# Arduino_Mega14x_V2.net
KiCad netlist of a schematic drawn in EAGLE
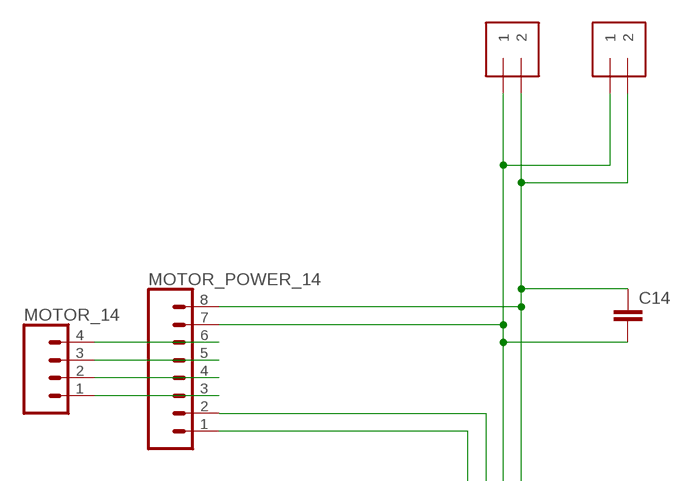
[diagram p0: schematic, sheet 1, part 1 of 3]
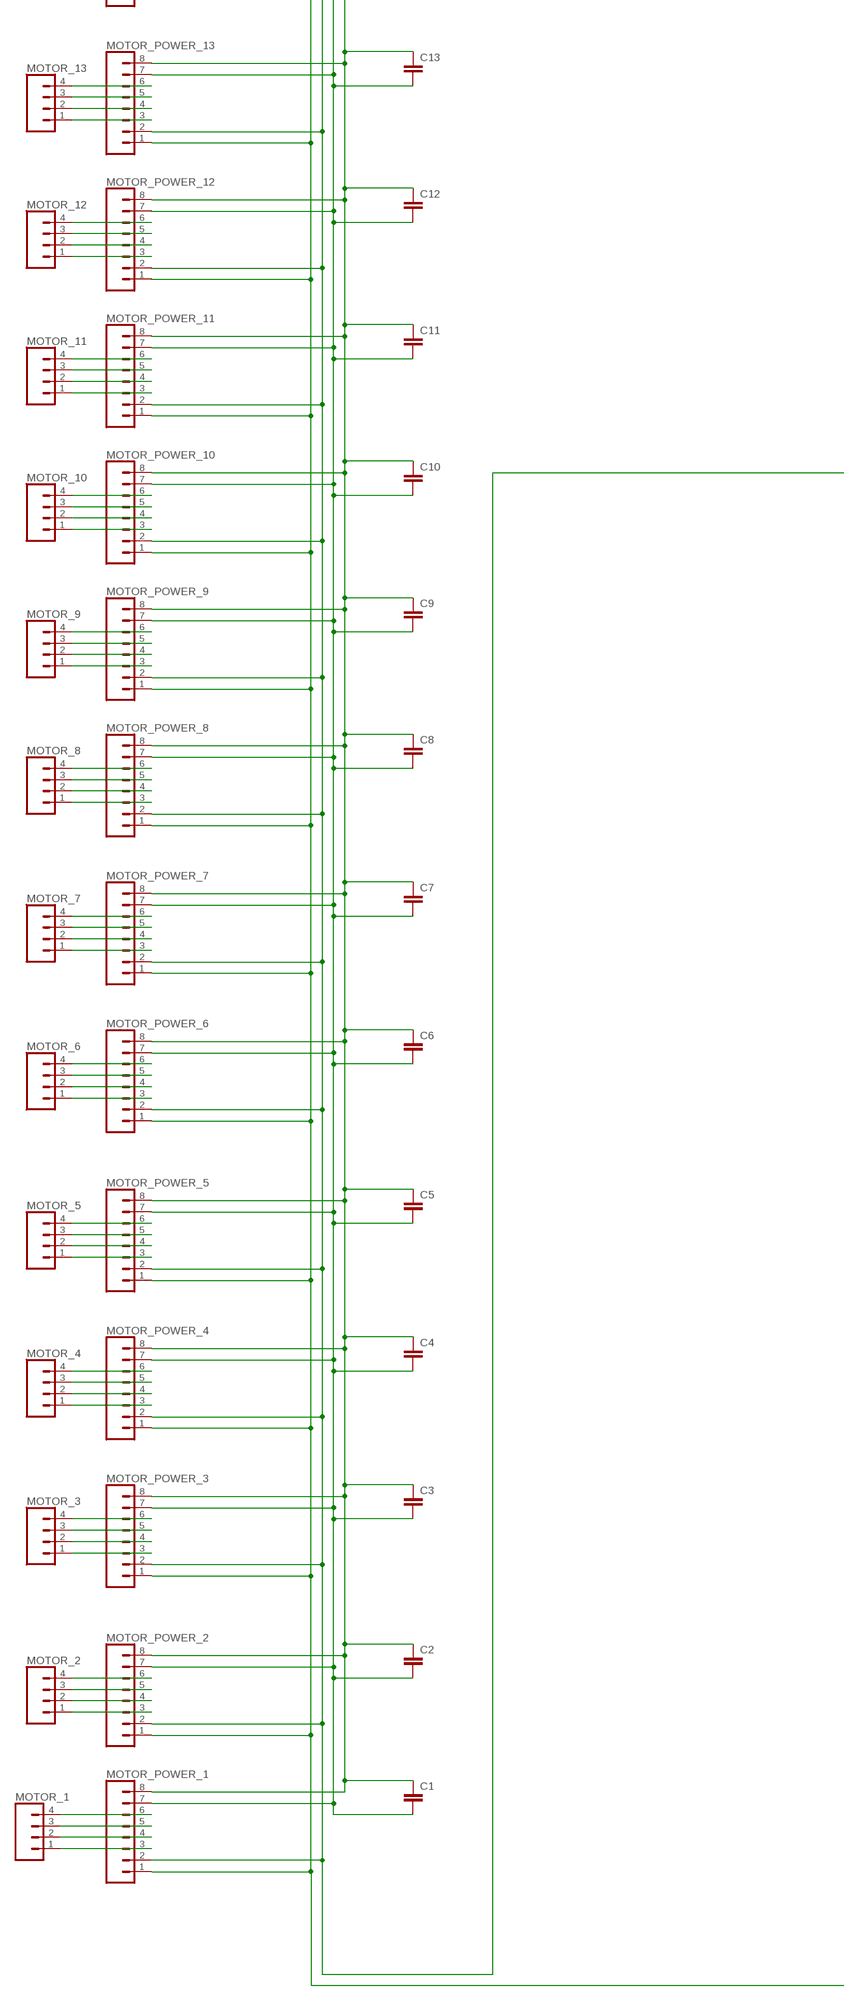
[diagram p1: schematic, sheet 1, part 2 of 3]
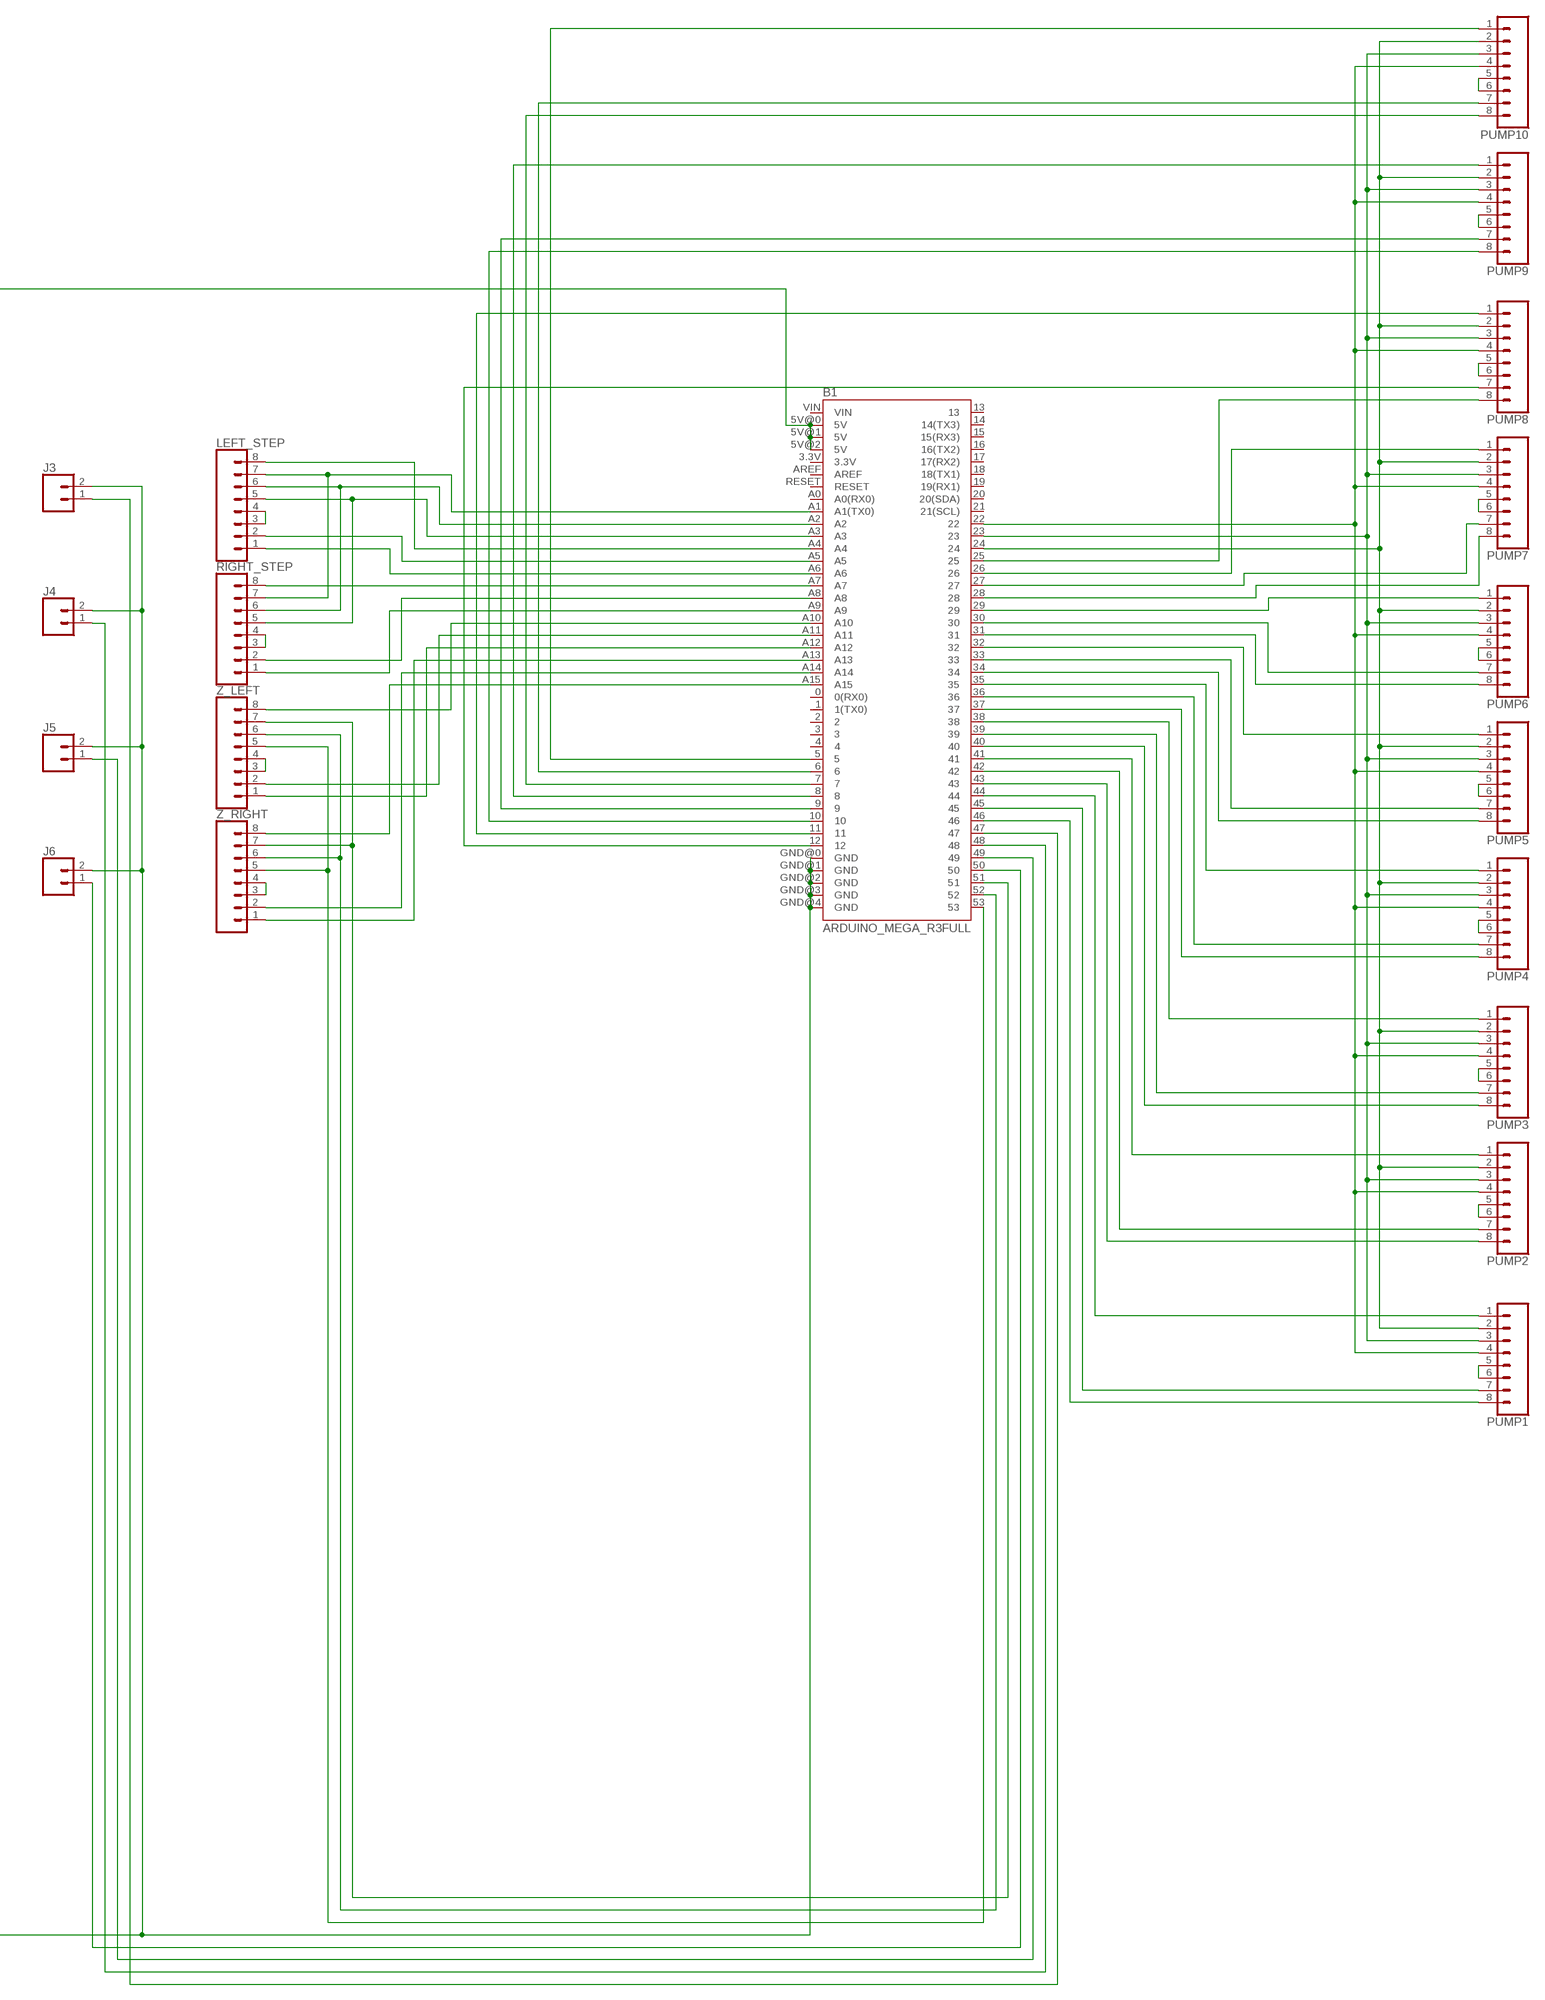
[diagram p2: schematic, sheet 1, part 3 of 3]

(export (version "E")
  (design (tool "Eeschema 10.0.6"))
  (components
    (comp (ref "B1")
      (value "ARDUINO_MEGA_R3FULL")
      (footprint "eagle-import:ARDUINO_MEGA")
      (libsource (lib "eagle-import") (part "ARDUINO_MEGA_R3FULL"))
    )
    (comp (ref "C1")
      (value "C5/2.5")
      (footprint "eagle-import:C5B2.5")
      (libsource (lib "eagle-import") (part "C5/2.5"))
    )
    (comp (ref "C2")
      (value "C5/2.5")
      (footprint "eagle-import:C5B2.5")
      (libsource (lib "eagle-import") (part "C5/2.5"))
    )
    (comp (ref "C3")
      (value "C5/2.5")
      (footprint "eagle-import:C5B2.5")
      (libsource (lib "eagle-import") (part "C5/2.5"))
    )
    (comp (ref "C4")
      (value "C5/2.5")
      (footprint "eagle-import:C5B2.5")
      (libsource (lib "eagle-import") (part "C5/2.5"))
    )
    (comp (ref "C5")
      (value "C5/2.5")
      (footprint "eagle-import:C5B2.5")
      (libsource (lib "eagle-import") (part "C5/2.5"))
    )
    (comp (ref "C6")
      (value "C5/2.5")
      (footprint "eagle-import:C5B2.5")
      (libsource (lib "eagle-import") (part "C5/2.5"))
    )
    (comp (ref "C7")
      (value "C5/2.5")
      (footprint "eagle-import:C5B2.5")
      (libsource (lib "eagle-import") (part "C5/2.5"))
    )
    (comp (ref "C8")
      (value "C5/2.5")
      (footprint "eagle-import:C5B2.5")
      (libsource (lib "eagle-import") (part "C5/2.5"))
    )
    (comp (ref "C9")
      (value "C5/2.5")
      (footprint "eagle-import:C5B2.5")
      (libsource (lib "eagle-import") (part "C5/2.5"))
    )
    (comp (ref "C10")
      (value "C5/2.5")
      (footprint "eagle-import:C5B2.5")
      (libsource (lib "eagle-import") (part "C5/2.5"))
    )
    (comp (ref "C11")
      (value "C5/2.5")
      (footprint "eagle-import:C5B2.5")
      (libsource (lib "eagle-import") (part "C5/2.5"))
    )
    (comp (ref "C12")
      (value "C5/2.5")
      (footprint "eagle-import:C5B2.5")
      (libsource (lib "eagle-import") (part "C5/2.5"))
    )
    (comp (ref "C13")
      (value "C5/2.5")
      (footprint "eagle-import:C5B2.5")
      (libsource (lib "eagle-import") (part "C5/2.5"))
    )
    (comp (ref "C14")
      (value "C5/2.5")
      (footprint "eagle-import:C5B2.5")
      (libsource (lib "eagle-import") (part "C5/2.5"))
    )
    (comp (ref "J1")
      (value "1X2-3.5MM")
      (footprint "eagle-import:1X2-3.5MM")
      (libsource (lib "eagle-import") (part "1X2-3.5MM"))
    )
    (comp (ref "J2")
      (value "1X2-3.5MM")
      (footprint "eagle-import:1X2-3.5MM")
      (libsource (lib "eagle-import") (part "1X2-3.5MM"))
    )
    (comp (ref "J3")
      (value "CONN_02")
      (footprint "eagle-import:1X02")
      (libsource (lib "eagle-import") (part "CONN_02"))
    )
    (comp (ref "J4")
      (value "CONN_02")
      (footprint "eagle-import:1X02")
      (libsource (lib "eagle-import") (part "CONN_02"))
    )
    (comp (ref "J5")
      (value "CONN_02")
      (footprint "eagle-import:1X02")
      (libsource (lib "eagle-import") (part "CONN_02"))
    )
    (comp (ref "J6")
      (value "CONN_02")
      (footprint "eagle-import:1X02")
      (libsource (lib "eagle-import") (part "CONN_02"))
    )
    (comp (ref "LEFT_STEP")
      (value "CONN_08\"")
      (footprint "eagle-import:1X08")
      (libsource (lib "eagle-import") (part "CONN_08{dblquote}"))
    )
    (comp (ref "MOTOR_1")
      (value "CONN_04")
      (footprint "eagle-import:1X04")
      (libsource (lib "eagle-import") (part "CONN_04"))
    )
    (comp (ref "MOTOR_2")
      (value "CONN_04")
      (footprint "eagle-import:1X04")
      (libsource (lib "eagle-import") (part "CONN_04"))
    )
    (comp (ref "MOTOR_3")
      (value "CONN_04")
      (footprint "eagle-import:1X04")
      (libsource (lib "eagle-import") (part "CONN_04"))
    )
    (comp (ref "MOTOR_4")
      (value "CONN_04")
      (footprint "eagle-import:1X04")
      (libsource (lib "eagle-import") (part "CONN_04"))
    )
    (comp (ref "MOTOR_5")
      (value "CONN_04")
      (footprint "eagle-import:1X04")
      (libsource (lib "eagle-import") (part "CONN_04"))
    )
    (comp (ref "MOTOR_6")
      (value "CONN_04")
      (footprint "eagle-import:1X04")
      (libsource (lib "eagle-import") (part "CONN_04"))
    )
    (comp (ref "MOTOR_7")
      (value "CONN_04")
      (footprint "eagle-import:1X04")
      (libsource (lib "eagle-import") (part "CONN_04"))
    )
    (comp (ref "MOTOR_8")
      (value "CONN_04")
      (footprint "eagle-import:1X04")
      (libsource (lib "eagle-import") (part "CONN_04"))
    )
    (comp (ref "MOTOR_9")
      (value "CONN_04")
      (footprint "eagle-import:1X04")
      (libsource (lib "eagle-import") (part "CONN_04"))
    )
    (comp (ref "MOTOR_10")
      (value "CONN_04")
      (footprint "eagle-import:1X04")
      (libsource (lib "eagle-import") (part "CONN_04"))
    )
    (comp (ref "MOTOR_11")
      (value "CONN_04")
      (footprint "eagle-import:1X04")
      (libsource (lib "eagle-import") (part "CONN_04"))
    )
    (comp (ref "MOTOR_12")
      (value "CONN_04")
      (footprint "eagle-import:1X04")
      (libsource (lib "eagle-import") (part "CONN_04"))
    )
    (comp (ref "MOTOR_13")
      (value "CONN_04")
      (footprint "eagle-import:1X04")
      (libsource (lib "eagle-import") (part "CONN_04"))
    )
    (comp (ref "MOTOR_14")
      (value "CONN_04")
      (footprint "eagle-import:1X04")
      (libsource (lib "eagle-import") (part "CONN_04"))
    )
    (comp (ref "MOTOR_POWER_1")
      (value "CONN_08\"")
      (footprint "eagle-import:1X08")
      (libsource (lib "eagle-import") (part "CONN_08{dblquote}"))
    )
    (comp (ref "MOTOR_POWER_2")
      (value "CONN_08\"")
      (footprint "eagle-import:1X08")
      (libsource (lib "eagle-import") (part "CONN_08{dblquote}"))
    )
    (comp (ref "MOTOR_POWER_3")
      (value "CONN_08\"")
      (footprint "eagle-import:1X08")
      (libsource (lib "eagle-import") (part "CONN_08{dblquote}"))
    )
    (comp (ref "MOTOR_POWER_4")
      (value "CONN_08\"")
      (footprint "eagle-import:1X08")
      (libsource (lib "eagle-import") (part "CONN_08{dblquote}"))
    )
    (comp (ref "MOTOR_POWER_5")
      (value "CONN_08\"")
      (footprint "eagle-import:1X08")
      (libsource (lib "eagle-import") (part "CONN_08{dblquote}"))
    )
    (comp (ref "MOTOR_POWER_6")
      (value "CONN_08\"")
      (footprint "eagle-import:1X08")
      (libsource (lib "eagle-import") (part "CONN_08{dblquote}"))
    )
    (comp (ref "MOTOR_POWER_7")
      (value "CONN_08\"")
      (footprint "eagle-import:1X08")
      (libsource (lib "eagle-import") (part "CONN_08{dblquote}"))
    )
    (comp (ref "MOTOR_POWER_8")
      (value "CONN_08\"")
      (footprint "eagle-import:1X08")
      (libsource (lib "eagle-import") (part "CONN_08{dblquote}"))
    )
    (comp (ref "MOTOR_POWER_9")
      (value "CONN_08\"")
      (footprint "eagle-import:1X08")
      (libsource (lib "eagle-import") (part "CONN_08{dblquote}"))
    )
    (comp (ref "MOTOR_POWER_10")
      (value "CONN_08\"")
      (footprint "eagle-import:1X08")
      (libsource (lib "eagle-import") (part "CONN_08{dblquote}"))
    )
    (comp (ref "MOTOR_POWER_11")
      (value "CONN_08\"")
      (footprint "eagle-import:1X08")
      (libsource (lib "eagle-import") (part "CONN_08{dblquote}"))
    )
    (comp (ref "MOTOR_POWER_12")
      (value "CONN_08\"")
      (footprint "eagle-import:1X08")
      (libsource (lib "eagle-import") (part "CONN_08{dblquote}"))
    )
    (comp (ref "MOTOR_POWER_13")
      (value "CONN_08\"")
      (footprint "eagle-import:1X08")
      (libsource (lib "eagle-import") (part "CONN_08{dblquote}"))
    )
    (comp (ref "MOTOR_POWER_14")
      (value "CONN_08\"")
      (footprint "eagle-import:1X08")
      (libsource (lib "eagle-import") (part "CONN_08{dblquote}"))
    )
    (comp (ref "PUMP1")
      (value "CONN_08\"")
      (footprint "eagle-import:1X08")
      (libsource (lib "eagle-import") (part "CONN_08{dblquote}"))
    )
    (comp (ref "PUMP2")
      (value "CONN_08\"")
      (footprint "eagle-import:1X08")
      (libsource (lib "eagle-import") (part "CONN_08{dblquote}"))
    )
    (comp (ref "PUMP3")
      (value "CONN_08\"")
      (footprint "eagle-import:1X08")
      (libsource (lib "eagle-import") (part "CONN_08{dblquote}"))
    )
    (comp (ref "PUMP4")
      (value "CONN_08\"")
      (footprint "eagle-import:1X08")
      (libsource (lib "eagle-import") (part "CONN_08{dblquote}"))
    )
    (comp (ref "PUMP5")
      (value "CONN_08\"")
      (footprint "eagle-import:1X08")
      (libsource (lib "eagle-import") (part "CONN_08{dblquote}"))
    )
    (comp (ref "PUMP6")
      (value "CONN_08\"")
      (footprint "eagle-import:1X08")
      (libsource (lib "eagle-import") (part "CONN_08{dblquote}"))
    )
    (comp (ref "PUMP7")
      (value "CONN_08\"")
      (footprint "eagle-import:1X08")
      (libsource (lib "eagle-import") (part "CONN_08{dblquote}"))
    )
    (comp (ref "PUMP8")
      (value "CONN_08\"")
      (footprint "eagle-import:1X08")
      (libsource (lib "eagle-import") (part "CONN_08{dblquote}"))
    )
    (comp (ref "PUMP9")
      (value "CONN_08\"")
      (footprint "eagle-import:1X08")
      (libsource (lib "eagle-import") (part "CONN_08{dblquote}"))
    )
    (comp (ref "PUMP10")
      (value "CONN_08\"")
      (footprint "eagle-import:1X08")
      (libsource (lib "eagle-import") (part "CONN_08{dblquote}"))
    )
    (comp (ref "RIGHT_STEP")
      (value "CONN_08\"")
      (footprint "eagle-import:1X08")
      (libsource (lib "eagle-import") (part "CONN_08{dblquote}"))
    )
    (comp (ref "Z_LEFT")
      (value "CONN_08\"")
      (footprint "eagle-import:1X08")
      (libsource (lib "eagle-import") (part "CONN_08{dblquote}"))
    )
    (comp (ref "Z_RIGHT")
      (value "CONN_08\"")
      (footprint "eagle-import:1X08")
      (libsource (lib "eagle-import") (part "CONN_08{dblquote}"))
    )
  )
  (nets
    (net (code "1") (name "Net-(B1-5V-Pad5V@0)") (class "Default")
      (node (ref "B1") (pin "5V@0") (pinfunction "5V_5V@0") (pintype "bidirectional"))
      (node (ref "B1") (pin "5V@1") (pinfunction "5V_5V@1") (pintype "bidirectional"))
      (node (ref "B1") (pin "5V@2") (pinfunction "5V_5V@2") (pintype "bidirectional"))
      (node (ref "MOTOR_POWER_1") (pin "2") (pinfunction "2_2") (pintype "passive"))
      (node (ref "MOTOR_POWER_10") (pin "2") (pinfunction "2_2") (pintype "passive"))
      (node (ref "MOTOR_POWER_11") (pin "2") (pinfunction "2_2") (pintype "passive"))
      (node (ref "MOTOR_POWER_12") (pin "2") (pinfunction "2_2") (pintype "passive"))
      (node (ref "MOTOR_POWER_13") (pin "2") (pinfunction "2_2") (pintype "passive"))
      (node (ref "MOTOR_POWER_14") (pin "2") (pinfunction "2_2") (pintype "passive"))
      (node (ref "MOTOR_POWER_2") (pin "2") (pinfunction "2_2") (pintype "passive"))
      (node (ref "MOTOR_POWER_3") (pin "2") (pinfunction "2_2") (pintype "passive"))
      (node (ref "MOTOR_POWER_4") (pin "2") (pinfunction "2_2") (pintype "passive"))
      (node (ref "MOTOR_POWER_5") (pin "2") (pinfunction "2_2") (pintype "passive"))
      (node (ref "MOTOR_POWER_6") (pin "2") (pinfunction "2_2") (pintype "passive"))
      (node (ref "MOTOR_POWER_7") (pin "2") (pinfunction "2_2") (pintype "passive"))
      (node (ref "MOTOR_POWER_8") (pin "2") (pinfunction "2_2") (pintype "passive"))
      (node (ref "MOTOR_POWER_9") (pin "2") (pinfunction "2_2") (pintype "passive"))
    )
    (net (code "2") (name "Net-(B1-A1(TX0))") (class "Default")
      (node (ref "B1") (pin "A1") (pinfunction "A1(TX0)_A1") (pintype "bidirectional"))
      (node (ref "LEFT_STEP") (pin "7") (pinfunction "7_7") (pintype "passive"))
      (node (ref "RIGHT_STEP") (pin "7") (pinfunction "7_7") (pintype "passive"))
    )
    (net (code "3") (name "Net-(B1-GND-PadGND@0)") (class "Default")
      (node (ref "B1") (pin "GND@0") (pinfunction "GND_GND@0") (pintype "bidirectional"))
      (node (ref "B1") (pin "GND@1") (pinfunction "GND_GND@1") (pintype "bidirectional"))
      (node (ref "B1") (pin "GND@2") (pinfunction "GND_GND@2") (pintype "bidirectional"))
      (node (ref "B1") (pin "GND@3") (pinfunction "GND_GND@3") (pintype "bidirectional"))
      (node (ref "B1") (pin "GND@4") (pinfunction "GND_GND@4") (pintype "bidirectional"))
      (node (ref "J3") (pin "2") (pinfunction "2_2") (pintype "passive"))
      (node (ref "J4") (pin "2") (pinfunction "2_2") (pintype "passive"))
      (node (ref "J5") (pin "2") (pinfunction "2_2") (pintype "passive"))
      (node (ref "J6") (pin "2") (pinfunction "2_2") (pintype "passive"))
      (node (ref "MOTOR_POWER_1") (pin "1") (pinfunction "1_1") (pintype "passive"))
      (node (ref "MOTOR_POWER_10") (pin "1") (pinfunction "1_1") (pintype "passive"))
      (node (ref "MOTOR_POWER_11") (pin "1") (pinfunction "1_1") (pintype "passive"))
      (node (ref "MOTOR_POWER_12") (pin "1") (pinfunction "1_1") (pintype "passive"))
      (node (ref "MOTOR_POWER_13") (pin "1") (pinfunction "1_1") (pintype "passive"))
      (node (ref "MOTOR_POWER_14") (pin "1") (pinfunction "1_1") (pintype "passive"))
      (node (ref "MOTOR_POWER_2") (pin "1") (pinfunction "1_1") (pintype "passive"))
      (node (ref "MOTOR_POWER_3") (pin "1") (pinfunction "1_1") (pintype "passive"))
      (node (ref "MOTOR_POWER_4") (pin "1") (pinfunction "1_1") (pintype "passive"))
      (node (ref "MOTOR_POWER_5") (pin "1") (pinfunction "1_1") (pintype "passive"))
      (node (ref "MOTOR_POWER_6") (pin "1") (pinfunction "1_1") (pintype "passive"))
      (node (ref "MOTOR_POWER_7") (pin "1") (pinfunction "1_1") (pintype "passive"))
      (node (ref "MOTOR_POWER_8") (pin "1") (pinfunction "1_1") (pintype "passive"))
      (node (ref "MOTOR_POWER_9") (pin "1") (pinfunction "1_1") (pintype "passive"))
    )
    (net (code "4") (name "Net-(B1-Pad5)") (class "Default")
      (node (ref "B1") (pin "5") (pinfunction "5_5") (pintype "bidirectional"))
      (node (ref "PUMP10") (pin "1") (pinfunction "1_1") (pintype "passive"))
    )
    (net (code "5") (name "Net-(B1-Pad6)") (class "Default")
      (node (ref "B1") (pin "6") (pinfunction "6_6") (pintype "bidirectional"))
      (node (ref "PUMP10") (pin "7") (pinfunction "7_7") (pintype "passive"))
    )
    (net (code "6") (name "Net-(B1-Pad7)") (class "Default")
      (node (ref "B1") (pin "7") (pinfunction "7_7") (pintype "bidirectional"))
      (node (ref "PUMP10") (pin "8") (pinfunction "8_8") (pintype "passive"))
    )
    (net (code "7") (name "Net-(B1-Pad8)") (class "Default")
      (node (ref "B1") (pin "8") (pinfunction "8_8") (pintype "bidirectional"))
      (node (ref "PUMP9") (pin "1") (pinfunction "1_1") (pintype "passive"))
    )
    (net (code "8") (name "Net-(B1-Pad9)") (class "Default")
      (node (ref "B1") (pin "9") (pinfunction "9_9") (pintype "bidirectional"))
      (node (ref "PUMP9") (pin "7") (pinfunction "7_7") (pintype "passive"))
    )
    (net (code "9") (name "Net-(B1-Pad10)") (class "Default")
      (node (ref "B1") (pin "10") (pinfunction "10_10") (pintype "bidirectional"))
      (node (ref "PUMP9") (pin "8") (pinfunction "8_8") (pintype "passive"))
    )
    (net (code "10") (name "Net-(B1-Pad11)") (class "Default")
      (node (ref "B1") (pin "11") (pinfunction "11_11") (pintype "bidirectional"))
      (node (ref "PUMP8") (pin "1") (pinfunction "1_1") (pintype "passive"))
    )
    (net (code "11") (name "Net-(B1-Pad12)") (class "Default")
      (node (ref "B1") (pin "12") (pinfunction "12_12") (pintype "bidirectional"))
      (node (ref "PUMP8") (pin "7") (pinfunction "7_7") (pintype "passive"))
    )
    (net (code "12") (name "Net-(B1-Pad22)") (class "Default")
      (node (ref "B1") (pin "22") (pinfunction "22_22") (pintype "bidirectional"))
      (node (ref "PUMP1") (pin "4") (pinfunction "4_4") (pintype "passive"))
      (node (ref "PUMP10") (pin "4") (pinfunction "4_4") (pintype "passive"))
      (node (ref "PUMP2") (pin "4") (pinfunction "4_4") (pintype "passive"))
      (node (ref "PUMP3") (pin "4") (pinfunction "4_4") (pintype "passive"))
      (node (ref "PUMP4") (pin "4") (pinfunction "4_4") (pintype "passive"))
      (node (ref "PUMP5") (pin "4") (pinfunction "4_4") (pintype "passive"))
      (node (ref "PUMP6") (pin "4") (pinfunction "4_4") (pintype "passive"))
      (node (ref "PUMP7") (pin "4") (pinfunction "4_4") (pintype "passive"))
      (node (ref "PUMP8") (pin "4") (pinfunction "4_4") (pintype "passive"))
      (node (ref "PUMP9") (pin "4") (pinfunction "4_4") (pintype "passive"))
    )
    (net (code "13") (name "Net-(B1-Pad23)") (class "Default")
      (node (ref "B1") (pin "23") (pinfunction "23_23") (pintype "bidirectional"))
      (node (ref "PUMP1") (pin "3") (pinfunction "3_3") (pintype "passive"))
      (node (ref "PUMP10") (pin "3") (pinfunction "3_3") (pintype "passive"))
      (node (ref "PUMP2") (pin "3") (pinfunction "3_3") (pintype "passive"))
      (node (ref "PUMP3") (pin "3") (pinfunction "3_3") (pintype "passive"))
      (node (ref "PUMP4") (pin "3") (pinfunction "3_3") (pintype "passive"))
      (node (ref "PUMP5") (pin "3") (pinfunction "3_3") (pintype "passive"))
      (node (ref "PUMP6") (pin "3") (pinfunction "3_3") (pintype "passive"))
      (node (ref "PUMP7") (pin "3") (pinfunction "3_3") (pintype "passive"))
      (node (ref "PUMP8") (pin "3") (pinfunction "3_3") (pintype "passive"))
      (node (ref "PUMP9") (pin "3") (pinfunction "3_3") (pintype "passive"))
    )
    (net (code "14") (name "Net-(B1-Pad24)") (class "Default")
      (node (ref "B1") (pin "24") (pinfunction "24_24") (pintype "bidirectional"))
      (node (ref "PUMP1") (pin "2") (pinfunction "2_2") (pintype "passive"))
      (node (ref "PUMP10") (pin "2") (pinfunction "2_2") (pintype "passive"))
      (node (ref "PUMP2") (pin "2") (pinfunction "2_2") (pintype "passive"))
      (node (ref "PUMP3") (pin "2") (pinfunction "2_2") (pintype "passive"))
      (node (ref "PUMP4") (pin "2") (pinfunction "2_2") (pintype "passive"))
      (node (ref "PUMP5") (pin "2") (pinfunction "2_2") (pintype "passive"))
      (node (ref "PUMP6") (pin "2") (pinfunction "2_2") (pintype "passive"))
      (node (ref "PUMP7") (pin "2") (pinfunction "2_2") (pintype "passive"))
      (node (ref "PUMP8") (pin "2") (pinfunction "2_2") (pintype "passive"))
      (node (ref "PUMP9") (pin "2") (pinfunction "2_2") (pintype "passive"))
    )
    (net (code "15") (name "Net-(B1-Pad25)") (class "Default")
      (node (ref "B1") (pin "25") (pinfunction "25_25") (pintype "bidirectional"))
      (node (ref "PUMP8") (pin "8") (pinfunction "8_8") (pintype "passive"))
    )
    (net (code "16") (name "Net-(B1-Pad26)") (class "Default")
      (node (ref "B1") (pin "26") (pinfunction "26_26") (pintype "bidirectional"))
      (node (ref "PUMP7") (pin "1") (pinfunction "1_1") (pintype "passive"))
    )
    (net (code "17") (name "Net-(B1-Pad27)") (class "Default")
      (node (ref "B1") (pin "27") (pinfunction "27_27") (pintype "bidirectional"))
      (node (ref "PUMP7") (pin "7") (pinfunction "7_7") (pintype "passive"))
    )
    (net (code "18") (name "Net-(B1-Pad28)") (class "Default")
      (node (ref "B1") (pin "28") (pinfunction "28_28") (pintype "bidirectional"))
      (node (ref "PUMP7") (pin "8") (pinfunction "8_8") (pintype "passive"))
    )
    (net (code "19") (name "Net-(B1-Pad29)") (class "Default")
      (node (ref "B1") (pin "29") (pinfunction "29_29") (pintype "bidirectional"))
      (node (ref "PUMP6") (pin "1") (pinfunction "1_1") (pintype "passive"))
    )
    (net (code "20") (name "Net-(B1-Pad30)") (class "Default")
      (node (ref "B1") (pin "30") (pinfunction "30_30") (pintype "bidirectional"))
      (node (ref "PUMP6") (pin "7") (pinfunction "7_7") (pintype "passive"))
    )
    (net (code "21") (name "Net-(B1-Pad31)") (class "Default")
      (node (ref "B1") (pin "31") (pinfunction "31_31") (pintype "bidirectional"))
      (node (ref "PUMP6") (pin "8") (pinfunction "8_8") (pintype "passive"))
    )
    (net (code "22") (name "Net-(B1-Pad32)") (class "Default")
      (node (ref "B1") (pin "32") (pinfunction "32_32") (pintype "bidirectional"))
      (node (ref "PUMP5") (pin "1") (pinfunction "1_1") (pintype "passive"))
    )
    (net (code "23") (name "Net-(B1-Pad33)") (class "Default")
      (node (ref "B1") (pin "33") (pinfunction "33_33") (pintype "bidirectional"))
      (node (ref "PUMP5") (pin "7") (pinfunction "7_7") (pintype "passive"))
    )
    (net (code "24") (name "Net-(B1-Pad34)") (class "Default")
      (node (ref "B1") (pin "34") (pinfunction "34_34") (pintype "bidirectional"))
      (node (ref "PUMP5") (pin "8") (pinfunction "8_8") (pintype "passive"))
    )
    (net (code "25") (name "Net-(B1-Pad35)") (class "Default")
      (node (ref "B1") (pin "35") (pinfunction "35_35") (pintype "bidirectional"))
      (node (ref "PUMP4") (pin "1") (pinfunction "1_1") (pintype "passive"))
    )
    (net (code "26") (name "Net-(B1-Pad36)") (class "Default")
      (node (ref "B1") (pin "36") (pinfunction "36_36") (pintype "bidirectional"))
      (node (ref "PUMP4") (pin "7") (pinfunction "7_7") (pintype "passive"))
    )
    (net (code "27") (name "Net-(B1-Pad37)") (class "Default")
      (node (ref "B1") (pin "37") (pinfunction "37_37") (pintype "bidirectional"))
      (node (ref "PUMP4") (pin "8") (pinfunction "8_8") (pintype "passive"))
    )
    (net (code "28") (name "Net-(B1-Pad38)") (class "Default")
      (node (ref "B1") (pin "38") (pinfunction "38_38") (pintype "bidirectional"))
      (node (ref "PUMP3") (pin "1") (pinfunction "1_1") (pintype "passive"))
    )
    (net (code "29") (name "Net-(B1-Pad39)") (class "Default")
      (node (ref "B1") (pin "39") (pinfunction "39_39") (pintype "bidirectional"))
      (node (ref "PUMP3") (pin "7") (pinfunction "7_7") (pintype "passive"))
    )
    (net (code "30") (name "Net-(B1-Pad40)") (class "Default")
      (node (ref "B1") (pin "40") (pinfunction "40_40") (pintype "bidirectional"))
      (node (ref "PUMP3") (pin "8") (pinfunction "8_8") (pintype "passive"))
    )
    (net (code "31") (name "Net-(B1-Pad41)") (class "Default")
      (node (ref "B1") (pin "41") (pinfunction "41_41") (pintype "bidirectional"))
      (node (ref "PUMP2") (pin "1") (pinfunction "1_1") (pintype "passive"))
    )
    (net (code "32") (name "Net-(B1-Pad42)") (class "Default")
      (node (ref "B1") (pin "42") (pinfunction "42_42") (pintype "bidirectional"))
      (node (ref "PUMP2") (pin "7") (pinfunction "7_7") (pintype "passive"))
    )
    (net (code "33") (name "Net-(B1-Pad43)") (class "Default")
      (node (ref "B1") (pin "43") (pinfunction "43_43") (pintype "bidirectional"))
      (node (ref "PUMP2") (pin "8") (pinfunction "8_8") (pintype "passive"))
    )
    (net (code "34") (name "Net-(B1-Pad44)") (class "Default")
      (node (ref "B1") (pin "44") (pinfunction "44_44") (pintype "bidirectional"))
      (node (ref "PUMP1") (pin "1") (pinfunction "1_1") (pintype "passive"))
    )
    (net (code "35") (name "Net-(B1-Pad45)") (class "Default")
      (node (ref "B1") (pin "45") (pinfunction "45_45") (pintype "bidirectional"))
      (node (ref "PUMP1") (pin "7") (pinfunction "7_7") (pintype "passive"))
    )
    (net (code "36") (name "Net-(B1-Pad46)") (class "Default")
      (node (ref "B1") (pin "46") (pinfunction "46_46") (pintype "bidirectional"))
      (node (ref "PUMP1") (pin "8") (pinfunction "8_8") (pintype "passive"))
    )
    (net (code "37") (name "Net-(B1-Pad47)") (class "Default")
      (node (ref "B1") (pin "47") (pinfunction "47_47") (pintype "bidirectional"))
      (node (ref "J3") (pin "1") (pinfunction "1_1") (pintype "passive"))
    )
    (net (code "38") (name "Net-(B1-Pad48)") (class "Default")
      (node (ref "B1") (pin "48") (pinfunction "48_48") (pintype "bidirectional"))
      (node (ref "J4") (pin "1") (pinfunction "1_1") (pintype "passive"))
    )
    (net (code "39") (name "Net-(B1-Pad49)") (class "Default")
      (node (ref "B1") (pin "49") (pinfunction "49_49") (pintype "bidirectional"))
      (node (ref "J5") (pin "1") (pinfunction "1_1") (pintype "passive"))
    )
    (net (code "40") (name "Net-(B1-Pad50)") (class "Default")
      (node (ref "B1") (pin "50") (pinfunction "50_50") (pintype "bidirectional"))
      (node (ref "J6") (pin "1") (pinfunction "1_1") (pintype "passive"))
    )
    (net (code "41") (name "Net-(B1-Pad51)") (class "Default")
      (node (ref "B1") (pin "51") (pinfunction "51_51") (pintype "bidirectional"))
      (node (ref "Z_LEFT") (pin "7") (pinfunction "7_7") (pintype "passive"))
      (node (ref "Z_RIGHT") (pin "7") (pinfunction "7_7") (pintype "passive"))
    )
    (net (code "42") (name "Net-(B1-Pad52)") (class "Default")
      (node (ref "B1") (pin "52") (pinfunction "52_52") (pintype "bidirectional"))
      (node (ref "Z_LEFT") (pin "6") (pinfunction "6_6") (pintype "passive"))
      (node (ref "Z_RIGHT") (pin "6") (pinfunction "6_6") (pintype "passive"))
    )
    (net (code "43") (name "Net-(B1-Pad53)") (class "Default")
      (node (ref "B1") (pin "53") (pinfunction "53_53") (pintype "bidirectional"))
      (node (ref "Z_LEFT") (pin "5") (pinfunction "5_5") (pintype "passive"))
      (node (ref "Z_RIGHT") (pin "5") (pinfunction "5_5") (pintype "passive"))
    )
    (net (code "44") (name "Net-(B1-PadA2)") (class "Default")
      (node (ref "B1") (pin "A2") (pinfunction "A2_A2") (pintype "bidirectional"))
      (node (ref "LEFT_STEP") (pin "6") (pinfunction "6_6") (pintype "passive"))
      (node (ref "RIGHT_STEP") (pin "6") (pinfunction "6_6") (pintype "passive"))
    )
    (net (code "45") (name "Net-(B1-PadA3)") (class "Default")
      (node (ref "B1") (pin "A3") (pinfunction "A3_A3") (pintype "bidirectional"))
      (node (ref "LEFT_STEP") (pin "5") (pinfunction "5_5") (pintype "passive"))
      (node (ref "RIGHT_STEP") (pin "5") (pinfunction "5_5") (pintype "passive"))
    )
    (net (code "46") (name "Net-(B1-PadA4)") (class "Default")
      (node (ref "B1") (pin "A4") (pinfunction "A4_A4") (pintype "bidirectional"))
      (node (ref "LEFT_STEP") (pin "8") (pinfunction "8_8") (pintype "passive"))
    )
    (net (code "47") (name "Net-(B1-PadA5)") (class "Default")
      (node (ref "B1") (pin "A5") (pinfunction "A5_A5") (pintype "bidirectional"))
      (node (ref "LEFT_STEP") (pin "2") (pinfunction "2_2") (pintype "passive"))
    )
    (net (code "48") (name "Net-(B1-PadA6)") (class "Default")
      (node (ref "B1") (pin "A6") (pinfunction "A6_A6") (pintype "bidirectional"))
      (node (ref "LEFT_STEP") (pin "1") (pinfunction "1_1") (pintype "passive"))
    )
    (net (code "49") (name "Net-(B1-PadA7)") (class "Default")
      (node (ref "B1") (pin "A7") (pinfunction "A7_A7") (pintype "bidirectional"))
      (node (ref "RIGHT_STEP") (pin "8") (pinfunction "8_8") (pintype "passive"))
    )
    (net (code "50") (name "Net-(B1-PadA8)") (class "Default")
      (node (ref "B1") (pin "A8") (pinfunction "A8_A8") (pintype "bidirectional"))
      (node (ref "RIGHT_STEP") (pin "2") (pinfunction "2_2") (pintype "passive"))
    )
    (net (code "51") (name "Net-(B1-PadA9)") (class "Default")
      (node (ref "B1") (pin "A9") (pinfunction "A9_A9") (pintype "bidirectional"))
      (node (ref "RIGHT_STEP") (pin "1") (pinfunction "1_1") (pintype "passive"))
    )
    (net (code "52") (name "Net-(B1-PadA10)") (class "Default")
      (node (ref "B1") (pin "A10") (pinfunction "A10_A10") (pintype "bidirectional"))
      (node (ref "Z_LEFT") (pin "8") (pinfunction "8_8") (pintype "passive"))
    )
    (net (code "53") (name "Net-(B1-PadA11)") (class "Default")
      (node (ref "B1") (pin "A11") (pinfunction "A11_A11") (pintype "bidirectional"))
      (node (ref "Z_LEFT") (pin "2") (pinfunction "2_2") (pintype "passive"))
    )
    (net (code "54") (name "Net-(B1-PadA12)") (class "Default")
      (node (ref "B1") (pin "A12") (pinfunction "A12_A12") (pintype "bidirectional"))
      (node (ref "Z_LEFT") (pin "1") (pinfunction "1_1") (pintype "passive"))
    )
    (net (code "55") (name "Net-(B1-PadA13)") (class "Default")
      (node (ref "B1") (pin "A13") (pinfunction "A13_A13") (pintype "bidirectional"))
      (node (ref "Z_RIGHT") (pin "1") (pinfunction "1_1") (pintype "passive"))
    )
    (net (code "56") (name "Net-(B1-PadA14)") (class "Default")
      (node (ref "B1") (pin "A14") (pinfunction "A14_A14") (pintype "bidirectional"))
      (node (ref "Z_RIGHT") (pin "2") (pinfunction "2_2") (pintype "passive"))
    )
    (net (code "57") (name "Net-(B1-PadA15)") (class "Default")
      (node (ref "B1") (pin "A15") (pinfunction "A15_A15") (pintype "bidirectional"))
      (node (ref "Z_RIGHT") (pin "8") (pinfunction "8_8") (pintype "passive"))
    )
    (net (code "58") (name "Net-(C1-Pad1)") (class "Default")
      (node (ref "C1") (pin "1") (pinfunction "1_1") (pintype "passive"))
      (node (ref "C10") (pin "1") (pinfunction "1_1") (pintype "passive"))
      (node (ref "C11") (pin "1") (pinfunction "1_1") (pintype "passive"))
      (node (ref "C12") (pin "1") (pinfunction "1_1") (pintype "passive"))
      (node (ref "C13") (pin "1") (pinfunction "1_1") (pintype "passive"))
      (node (ref "C14") (pin "1") (pinfunction "1_1") (pintype "passive"))
      (node (ref "C2") (pin "1") (pinfunction "1_1") (pintype "passive"))
      (node (ref "C3") (pin "1") (pinfunction "1_1") (pintype "passive"))
      (node (ref "C4") (pin "1") (pinfunction "1_1") (pintype "passive"))
      (node (ref "C5") (pin "1") (pinfunction "1_1") (pintype "passive"))
      (node (ref "C6") (pin "1") (pinfunction "1_1") (pintype "passive"))
      (node (ref "C7") (pin "1") (pinfunction "1_1") (pintype "passive"))
      (node (ref "C8") (pin "1") (pinfunction "1_1") (pintype "passive"))
      (node (ref "C9") (pin "1") (pinfunction "1_1") (pintype "passive"))
      (node (ref "J1") (pin "2") (pinfunction "2_2") (pintype "passive"))
      (node (ref "J2") (pin "2") (pinfunction "2_2") (pintype "passive"))
      (node (ref "MOTOR_POWER_1") (pin "8") (pinfunction "8_8") (pintype "passive"))
      (node (ref "MOTOR_POWER_10") (pin "8") (pinfunction "8_8") (pintype "passive"))
      (node (ref "MOTOR_POWER_11") (pin "8") (pinfunction "8_8") (pintype "passive"))
      (node (ref "MOTOR_POWER_12") (pin "8") (pinfunction "8_8") (pintype "passive"))
      (node (ref "MOTOR_POWER_13") (pin "8") (pinfunction "8_8") (pintype "passive"))
      (node (ref "MOTOR_POWER_14") (pin "8") (pinfunction "8_8") (pintype "passive"))
      (node (ref "MOTOR_POWER_2") (pin "8") (pinfunction "8_8") (pintype "passive"))
      (node (ref "MOTOR_POWER_3") (pin "8") (pinfunction "8_8") (pintype "passive"))
      (node (ref "MOTOR_POWER_4") (pin "8") (pinfunction "8_8") (pintype "passive"))
      (node (ref "MOTOR_POWER_5") (pin "8") (pinfunction "8_8") (pintype "passive"))
      (node (ref "MOTOR_POWER_6") (pin "8") (pinfunction "8_8") (pintype "passive"))
      (node (ref "MOTOR_POWER_7") (pin "8") (pinfunction "8_8") (pintype "passive"))
      (node (ref "MOTOR_POWER_8") (pin "8") (pinfunction "8_8") (pintype "passive"))
      (node (ref "MOTOR_POWER_9") (pin "8") (pinfunction "8_8") (pintype "passive"))
    )
    (net (code "59") (name "Net-(C1-Pad2)") (class "Default")
      (node (ref "C1") (pin "2") (pinfunction "2_2") (pintype "passive"))
      (node (ref "C10") (pin "2") (pinfunction "2_2") (pintype "passive"))
      (node (ref "C11") (pin "2") (pinfunction "2_2") (pintype "passive"))
      (node (ref "C12") (pin "2") (pinfunction "2_2") (pintype "passive"))
      (node (ref "C13") (pin "2") (pinfunction "2_2") (pintype "passive"))
      (node (ref "C14") (pin "2") (pinfunction "2_2") (pintype "passive"))
      (node (ref "C2") (pin "2") (pinfunction "2_2") (pintype "passive"))
      (node (ref "C3") (pin "2") (pinfunction "2_2") (pintype "passive"))
      (node (ref "C4") (pin "2") (pinfunction "2_2") (pintype "passive"))
      (node (ref "C5") (pin "2") (pinfunction "2_2") (pintype "passive"))
      (node (ref "C6") (pin "2") (pinfunction "2_2") (pintype "passive"))
      (node (ref "C7") (pin "2") (pinfunction "2_2") (pintype "passive"))
      (node (ref "C8") (pin "2") (pinfunction "2_2") (pintype "passive"))
      (node (ref "C9") (pin "2") (pinfunction "2_2") (pintype "passive"))
      (node (ref "J1") (pin "1") (pinfunction "1_1") (pintype "passive"))
      (node (ref "J2") (pin "1") (pinfunction "1_1") (pintype "passive"))
      (node (ref "MOTOR_POWER_1") (pin "7") (pinfunction "7_7") (pintype "passive"))
      (node (ref "MOTOR_POWER_10") (pin "7") (pinfunction "7_7") (pintype "passive"))
      (node (ref "MOTOR_POWER_11") (pin "7") (pinfunction "7_7") (pintype "passive"))
      (node (ref "MOTOR_POWER_12") (pin "7") (pinfunction "7_7") (pintype "passive"))
      (node (ref "MOTOR_POWER_13") (pin "7") (pinfunction "7_7") (pintype "passive"))
      (node (ref "MOTOR_POWER_14") (pin "7") (pinfunction "7_7") (pintype "passive"))
      (node (ref "MOTOR_POWER_2") (pin "7") (pinfunction "7_7") (pintype "passive"))
      (node (ref "MOTOR_POWER_3") (pin "7") (pinfunction "7_7") (pintype "passive"))
      (node (ref "MOTOR_POWER_4") (pin "7") (pinfunction "7_7") (pintype "passive"))
      (node (ref "MOTOR_POWER_5") (pin "7") (pinfunction "7_7") (pintype "passive"))
      (node (ref "MOTOR_POWER_6") (pin "7") (pinfunction "7_7") (pintype "passive"))
      (node (ref "MOTOR_POWER_7") (pin "7") (pinfunction "7_7") (pintype "passive"))
      (node (ref "MOTOR_POWER_8") (pin "7") (pinfunction "7_7") (pintype "passive"))
      (node (ref "MOTOR_POWER_9") (pin "7") (pinfunction "7_7") (pintype "passive"))
    )
    (net (code "60") (name "Net-(LEFT_STEP-Pad3)") (class "Default")
      (node (ref "LEFT_STEP") (pin "3") (pinfunction "3_3") (pintype "passive"))
      (node (ref "LEFT_STEP") (pin "4") (pinfunction "4_4") (pintype "passive"))
    )
    (net (code "61") (name "Net-(MOTOR_1-Pad1)") (class "Default")
      (node (ref "MOTOR_1") (pin "1") (pinfunction "1_1") (pintype "passive"))
      (node (ref "MOTOR_POWER_1") (pin "3") (pinfunction "3_3") (pintype "passive"))
    )
    (net (code "62") (name "Net-(MOTOR_1-Pad2)") (class "Default")
      (node (ref "MOTOR_1") (pin "2") (pinfunction "2_2") (pintype "passive"))
      (node (ref "MOTOR_POWER_1") (pin "4") (pinfunction "4_4") (pintype "passive"))
    )
    (net (code "63") (name "Net-(MOTOR_1-Pad3)") (class "Default")
      (node (ref "MOTOR_1") (pin "3") (pinfunction "3_3") (pintype "passive"))
      (node (ref "MOTOR_POWER_1") (pin "5") (pinfunction "5_5") (pintype "passive"))
    )
    (net (code "64") (name "Net-(MOTOR_1-Pad4)") (class "Default")
      (node (ref "MOTOR_1") (pin "4") (pinfunction "4_4") (pintype "passive"))
      (node (ref "MOTOR_POWER_1") (pin "6") (pinfunction "6_6") (pintype "passive"))
    )
    (net (code "65") (name "Net-(MOTOR_2-Pad1)") (class "Default")
      (node (ref "MOTOR_2") (pin "1") (pinfunction "1_1") (pintype "passive"))
      (node (ref "MOTOR_POWER_2") (pin "3") (pinfunction "3_3") (pintype "passive"))
    )
    (net (code "66") (name "Net-(MOTOR_2-Pad2)") (class "Default")
      (node (ref "MOTOR_2") (pin "2") (pinfunction "2_2") (pintype "passive"))
      (node (ref "MOTOR_POWER_2") (pin "4") (pinfunction "4_4") (pintype "passive"))
    )
    (net (code "67") (name "Net-(MOTOR_2-Pad3)") (class "Default")
      (node (ref "MOTOR_2") (pin "3") (pinfunction "3_3") (pintype "passive"))
      (node (ref "MOTOR_POWER_2") (pin "5") (pinfunction "5_5") (pintype "passive"))
    )
    (net (code "68") (name "Net-(MOTOR_2-Pad4)") (class "Default")
      (node (ref "MOTOR_2") (pin "4") (pinfunction "4_4") (pintype "passive"))
      (node (ref "MOTOR_POWER_2") (pin "6") (pinfunction "6_6") (pintype "passive"))
    )
    (net (code "69") (name "Net-(MOTOR_3-Pad1)") (class "Default")
      (node (ref "MOTOR_3") (pin "1") (pinfunction "1_1") (pintype "passive"))
      (node (ref "MOTOR_POWER_3") (pin "3") (pinfunction "3_3") (pintype "passive"))
    )
    (net (code "70") (name "Net-(MOTOR_3-Pad2)") (class "Default")
      (node (ref "MOTOR_3") (pin "2") (pinfunction "2_2") (pintype "passive"))
      (node (ref "MOTOR_POWER_3") (pin "4") (pinfunction "4_4") (pintype "passive"))
    )
    (net (code "71") (name "Net-(MOTOR_3-Pad3)") (class "Default")
      (node (ref "MOTOR_3") (pin "3") (pinfunction "3_3") (pintype "passive"))
      (node (ref "MOTOR_POWER_3") (pin "5") (pinfunction "5_5") (pintype "passive"))
    )
    (net (code "72") (name "Net-(MOTOR_3-Pad4)") (class "Default")
      (node (ref "MOTOR_3") (pin "4") (pinfunction "4_4") (pintype "passive"))
      (node (ref "MOTOR_POWER_3") (pin "6") (pinfunction "6_6") (pintype "passive"))
    )
    (net (code "73") (name "Net-(MOTOR_4-Pad1)") (class "Default")
      (node (ref "MOTOR_4") (pin "1") (pinfunction "1_1") (pintype "passive"))
      (node (ref "MOTOR_POWER_4") (pin "3") (pinfunction "3_3") (pintype "passive"))
    )
    (net (code "74") (name "Net-(MOTOR_4-Pad2)") (class "Default")
      (node (ref "MOTOR_4") (pin "2") (pinfunction "2_2") (pintype "passive"))
      (node (ref "MOTOR_POWER_4") (pin "4") (pinfunction "4_4") (pintype "passive"))
    )
    (net (code "75") (name "Net-(MOTOR_4-Pad3)") (class "Default")
      (node (ref "MOTOR_4") (pin "3") (pinfunction "3_3") (pintype "passive"))
      (node (ref "MOTOR_POWER_4") (pin "5") (pinfunction "5_5") (pintype "passive"))
    )
    (net (code "76") (name "Net-(MOTOR_4-Pad4)") (class "Default")
      (node (ref "MOTOR_4") (pin "4") (pinfunction "4_4") (pintype "passive"))
      (node (ref "MOTOR_POWER_4") (pin "6") (pinfunction "6_6") (pintype "passive"))
    )
    (net (code "77") (name "Net-(MOTOR_5-Pad1)") (class "Default")
      (node (ref "MOTOR_5") (pin "1") (pinfunction "1_1") (pintype "passive"))
      (node (ref "MOTOR_POWER_5") (pin "3") (pinfunction "3_3") (pintype "passive"))
    )
    (net (code "78") (name "Net-(MOTOR_5-Pad2)") (class "Default")
      (node (ref "MOTOR_5") (pin "2") (pinfunction "2_2") (pintype "passive"))
      (node (ref "MOTOR_POWER_5") (pin "4") (pinfunction "4_4") (pintype "passive"))
    )
    (net (code "79") (name "Net-(MOTOR_5-Pad3)") (class "Default")
      (node (ref "MOTOR_5") (pin "3") (pinfunction "3_3") (pintype "passive"))
      (node (ref "MOTOR_POWER_5") (pin "5") (pinfunction "5_5") (pintype "passive"))
    )
    (net (code "80") (name "Net-(MOTOR_5-Pad4)") (class "Default")
      (node (ref "MOTOR_5") (pin "4") (pinfunction "4_4") (pintype "passive"))
      (node (ref "MOTOR_POWER_5") (pin "6") (pinfunction "6_6") (pintype "passive"))
    )
    (net (code "81") (name "Net-(MOTOR_6-Pad1)") (class "Default")
      (node (ref "MOTOR_6") (pin "1") (pinfunction "1_1") (pintype "passive"))
      (node (ref "MOTOR_POWER_6") (pin "3") (pinfunction "3_3") (pintype "passive"))
    )
    (net (code "82") (name "Net-(MOTOR_6-Pad2)") (class "Default")
      (node (ref "MOTOR_6") (pin "2") (pinfunction "2_2") (pintype "passive"))
      (node (ref "MOTOR_POWER_6") (pin "4") (pinfunction "4_4") (pintype "passive"))
    )
    (net (code "83") (name "Net-(MOTOR_6-Pad3)") (class "Default")
      (node (ref "MOTOR_6") (pin "3") (pinfunction "3_3") (pintype "passive"))
      (node (ref "MOTOR_POWER_6") (pin "5") (pinfunction "5_5") (pintype "passive"))
    )
    (net (code "84") (name "Net-(MOTOR_6-Pad4)") (class "Default")
      (node (ref "MOTOR_6") (pin "4") (pinfunction "4_4") (pintype "passive"))
      (node (ref "MOTOR_POWER_6") (pin "6") (pinfunction "6_6") (pintype "passive"))
    )
    (net (code "85") (name "Net-(MOTOR_7-Pad1)") (class "Default")
      (node (ref "MOTOR_7") (pin "1") (pinfunction "1_1") (pintype "passive"))
      (node (ref "MOTOR_POWER_7") (pin "3") (pinfunction "3_3") (pintype "passive"))
    )
    (net (code "86") (name "Net-(MOTOR_7-Pad2)") (class "Default")
      (node (ref "MOTOR_7") (pin "2") (pinfunction "2_2") (pintype "passive"))
      (node (ref "MOTOR_POWER_7") (pin "4") (pinfunction "4_4") (pintype "passive"))
    )
    (net (code "87") (name "Net-(MOTOR_7-Pad3)") (class "Default")
      (node (ref "MOTOR_7") (pin "3") (pinfunction "3_3") (pintype "passive"))
      (node (ref "MOTOR_POWER_7") (pin "5") (pinfunction "5_5") (pintype "passive"))
    )
    (net (code "88") (name "Net-(MOTOR_7-Pad4)") (class "Default")
      (node (ref "MOTOR_7") (pin "4") (pinfunction "4_4") (pintype "passive"))
      (node (ref "MOTOR_POWER_7") (pin "6") (pinfunction "6_6") (pintype "passive"))
    )
    (net (code "89") (name "Net-(MOTOR_8-Pad1)") (class "Default")
      (node (ref "MOTOR_8") (pin "1") (pinfunction "1_1") (pintype "passive"))
      (node (ref "MOTOR_POWER_8") (pin "3") (pinfunction "3_3") (pintype "passive"))
    )
    (net (code "90") (name "Net-(MOTOR_8-Pad2)") (class "Default")
      (node (ref "MOTOR_8") (pin "2") (pinfunction "2_2") (pintype "passive"))
      (node (ref "MOTOR_POWER_8") (pin "4") (pinfunction "4_4") (pintype "passive"))
    )
    (net (code "91") (name "Net-(MOTOR_8-Pad3)") (class "Default")
      (node (ref "MOTOR_8") (pin "3") (pinfunction "3_3") (pintype "passive"))
      (node (ref "MOTOR_POWER_8") (pin "5") (pinfunction "5_5") (pintype "passive"))
    )
    (net (code "92") (name "Net-(MOTOR_8-Pad4)") (class "Default")
      (node (ref "MOTOR_8") (pin "4") (pinfunction "4_4") (pintype "passive"))
      (node (ref "MOTOR_POWER_8") (pin "6") (pinfunction "6_6") (pintype "passive"))
    )
    (net (code "93") (name "Net-(MOTOR_9-Pad1)") (class "Default")
      (node (ref "MOTOR_9") (pin "1") (pinfunction "1_1") (pintype "passive"))
      (node (ref "MOTOR_POWER_9") (pin "3") (pinfunction "3_3") (pintype "passive"))
    )
    (net (code "94") (name "Net-(MOTOR_9-Pad2)") (class "Default")
      (node (ref "MOTOR_9") (pin "2") (pinfunction "2_2") (pintype "passive"))
      (node (ref "MOTOR_POWER_9") (pin "4") (pinfunction "4_4") (pintype "passive"))
    )
    (net (code "95") (name "Net-(MOTOR_9-Pad3)") (class "Default")
      (node (ref "MOTOR_9") (pin "3") (pinfunction "3_3") (pintype "passive"))
      (node (ref "MOTOR_POWER_9") (pin "5") (pinfunction "5_5") (pintype "passive"))
    )
    (net (code "96") (name "Net-(MOTOR_9-Pad4)") (class "Default")
      (node (ref "MOTOR_9") (pin "4") (pinfunction "4_4") (pintype "passive"))
      (node (ref "MOTOR_POWER_9") (pin "6") (pinfunction "6_6") (pintype "passive"))
    )
    (net (code "97") (name "Net-(MOTOR_10-Pad1)") (class "Default")
      (node (ref "MOTOR_10") (pin "1") (pinfunction "1_1") (pintype "passive"))
      (node (ref "MOTOR_POWER_10") (pin "3") (pinfunction "3_3") (pintype "passive"))
    )
    (net (code "98") (name "Net-(MOTOR_10-Pad2)") (class "Default")
      (node (ref "MOTOR_10") (pin "2") (pinfunction "2_2") (pintype "passive"))
      (node (ref "MOTOR_POWER_10") (pin "4") (pinfunction "4_4") (pintype "passive"))
    )
    (net (code "99") (name "Net-(MOTOR_10-Pad3)") (class "Default")
      (node (ref "MOTOR_10") (pin "3") (pinfunction "3_3") (pintype "passive"))
      (node (ref "MOTOR_POWER_10") (pin "5") (pinfunction "5_5") (pintype "passive"))
    )
    (net (code "100") (name "Net-(MOTOR_10-Pad4)") (class "Default")
      (node (ref "MOTOR_10") (pin "4") (pinfunction "4_4") (pintype "passive"))
      (node (ref "MOTOR_POWER_10") (pin "6") (pinfunction "6_6") (pintype "passive"))
    )
    (net (code "101") (name "Net-(MOTOR_11-Pad1)") (class "Default")
      (node (ref "MOTOR_11") (pin "1") (pinfunction "1_1") (pintype "passive"))
      (node (ref "MOTOR_POWER_11") (pin "3") (pinfunction "3_3") (pintype "passive"))
    )
    (net (code "102") (name "Net-(MOTOR_11-Pad2)") (class "Default")
      (node (ref "MOTOR_11") (pin "2") (pinfunction "2_2") (pintype "passive"))
      (node (ref "MOTOR_POWER_11") (pin "4") (pinfunction "4_4") (pintype "passive"))
    )
    (net (code "103") (name "Net-(MOTOR_11-Pad3)") (class "Default")
      (node (ref "MOTOR_11") (pin "3") (pinfunction "3_3") (pintype "passive"))
      (node (ref "MOTOR_POWER_11") (pin "5") (pinfunction "5_5") (pintype "passive"))
    )
    (net (code "104") (name "Net-(MOTOR_11-Pad4)") (class "Default")
      (node (ref "MOTOR_11") (pin "4") (pinfunction "4_4") (pintype "passive"))
      (node (ref "MOTOR_POWER_11") (pin "6") (pinfunction "6_6") (pintype "passive"))
    )
    (net (code "105") (name "Net-(MOTOR_12-Pad1)") (class "Default")
      (node (ref "MOTOR_12") (pin "1") (pinfunction "1_1") (pintype "passive"))
      (node (ref "MOTOR_POWER_12") (pin "3") (pinfunction "3_3") (pintype "passive"))
    )
    (net (code "106") (name "Net-(MOTOR_12-Pad2)") (class "Default")
      (node (ref "MOTOR_12") (pin "2") (pinfunction "2_2") (pintype "passive"))
      (node (ref "MOTOR_POWER_12") (pin "4") (pinfunction "4_4") (pintype "passive"))
    )
    (net (code "107") (name "Net-(MOTOR_12-Pad3)") (class "Default")
      (node (ref "MOTOR_12") (pin "3") (pinfunction "3_3") (pintype "passive"))
      (node (ref "MOTOR_POWER_12") (pin "5") (pinfunction "5_5") (pintype "passive"))
    )
    (net (code "108") (name "Net-(MOTOR_12-Pad4)") (class "Default")
      (node (ref "MOTOR_12") (pin "4") (pinfunction "4_4") (pintype "passive"))
      (node (ref "MOTOR_POWER_12") (pin "6") (pinfunction "6_6") (pintype "passive"))
    )
    (net (code "109") (name "Net-(MOTOR_13-Pad1)") (class "Default")
      (node (ref "MOTOR_13") (pin "1") (pinfunction "1_1") (pintype "passive"))
      (node (ref "MOTOR_POWER_13") (pin "3") (pinfunction "3_3") (pintype "passive"))
    )
    (net (code "110") (name "Net-(MOTOR_13-Pad2)") (class "Default")
      (node (ref "MOTOR_13") (pin "2") (pinfunction "2_2") (pintype "passive"))
      (node (ref "MOTOR_POWER_13") (pin "4") (pinfunction "4_4") (pintype "passive"))
    )
    (net (code "111") (name "Net-(MOTOR_13-Pad3)") (class "Default")
      (node (ref "MOTOR_13") (pin "3") (pinfunction "3_3") (pintype "passive"))
      (node (ref "MOTOR_POWER_13") (pin "5") (pinfunction "5_5") (pintype "passive"))
    )
    (net (code "112") (name "Net-(MOTOR_13-Pad4)") (class "Default")
      (node (ref "MOTOR_13") (pin "4") (pinfunction "4_4") (pintype "passive"))
      (node (ref "MOTOR_POWER_13") (pin "6") (pinfunction "6_6") (pintype "passive"))
    )
    (net (code "113") (name "Net-(MOTOR_14-Pad1)") (class "Default")
      (node (ref "MOTOR_14") (pin "1") (pinfunction "1_1") (pintype "passive"))
      (node (ref "MOTOR_POWER_14") (pin "3") (pinfunction "3_3") (pintype "passive"))
    )
    (net (code "114") (name "Net-(MOTOR_14-Pad2)") (class "Default")
      (node (ref "MOTOR_14") (pin "2") (pinfunction "2_2") (pintype "passive"))
      (node (ref "MOTOR_POWER_14") (pin "4") (pinfunction "4_4") (pintype "passive"))
    )
    (net (code "115") (name "Net-(MOTOR_14-Pad3)") (class "Default")
      (node (ref "MOTOR_14") (pin "3") (pinfunction "3_3") (pintype "passive"))
      (node (ref "MOTOR_POWER_14") (pin "5") (pinfunction "5_5") (pintype "passive"))
    )
    (net (code "116") (name "Net-(MOTOR_14-Pad4)") (class "Default")
      (node (ref "MOTOR_14") (pin "4") (pinfunction "4_4") (pintype "passive"))
      (node (ref "MOTOR_POWER_14") (pin "6") (pinfunction "6_6") (pintype "passive"))
    )
    (net (code "117") (name "Net-(PUMP1-Pad5)") (class "Default")
      (node (ref "PUMP1") (pin "5") (pinfunction "5_5") (pintype "passive"))
      (node (ref "PUMP1") (pin "6") (pinfunction "6_6") (pintype "passive"))
    )
    (net (code "118") (name "Net-(PUMP2-Pad5)") (class "Default")
      (node (ref "PUMP2") (pin "5") (pinfunction "5_5") (pintype "passive"))
      (node (ref "PUMP2") (pin "6") (pinfunction "6_6") (pintype "passive"))
    )
    (net (code "119") (name "Net-(PUMP3-Pad5)") (class "Default")
      (node (ref "PUMP3") (pin "5") (pinfunction "5_5") (pintype "passive"))
      (node (ref "PUMP3") (pin "6") (pinfunction "6_6") (pintype "passive"))
    )
    (net (code "120") (name "Net-(PUMP4-Pad5)") (class "Default")
      (node (ref "PUMP4") (pin "5") (pinfunction "5_5") (pintype "passive"))
      (node (ref "PUMP4") (pin "6") (pinfunction "6_6") (pintype "passive"))
    )
    (net (code "121") (name "Net-(PUMP5-Pad5)") (class "Default")
      (node (ref "PUMP5") (pin "5") (pinfunction "5_5") (pintype "passive"))
      (node (ref "PUMP5") (pin "6") (pinfunction "6_6") (pintype "passive"))
    )
    (net (code "122") (name "Net-(PUMP6-Pad5)") (class "Default")
      (node (ref "PUMP6") (pin "5") (pinfunction "5_5") (pintype "passive"))
      (node (ref "PUMP6") (pin "6") (pinfunction "6_6") (pintype "passive"))
    )
    (net (code "123") (name "Net-(PUMP7-Pad5)") (class "Default")
      (node (ref "PUMP7") (pin "5") (pinfunction "5_5") (pintype "passive"))
      (node (ref "PUMP7") (pin "6") (pinfunction "6_6") (pintype "passive"))
    )
    (net (code "124") (name "Net-(PUMP8-Pad5)") (class "Default")
      (node (ref "PUMP8") (pin "5") (pinfunction "5_5") (pintype "passive"))
      (node (ref "PUMP8") (pin "6") (pinfunction "6_6") (pintype "passive"))
    )
    (net (code "125") (name "Net-(PUMP9-Pad5)") (class "Default")
      (node (ref "PUMP9") (pin "5") (pinfunction "5_5") (pintype "passive"))
      (node (ref "PUMP9") (pin "6") (pinfunction "6_6") (pintype "passive"))
    )
    (net (code "126") (name "Net-(PUMP10-Pad5)") (class "Default")
      (node (ref "PUMP10") (pin "5") (pinfunction "5_5") (pintype "passive"))
      (node (ref "PUMP10") (pin "6") (pinfunction "6_6") (pintype "passive"))
    )
    (net (code "127") (name "Net-(RIGHT_STEP-Pad3)") (class "Default")
      (node (ref "RIGHT_STEP") (pin "3") (pinfunction "3_3") (pintype "passive"))
      (node (ref "RIGHT_STEP") (pin "4") (pinfunction "4_4") (pintype "passive"))
    )
    (net (code "128") (name "Net-(Z_LEFT-Pad3)") (class "Default")
      (node (ref "Z_LEFT") (pin "3") (pinfunction "3_3") (pintype "passive"))
      (node (ref "Z_LEFT") (pin "4") (pinfunction "4_4") (pintype "passive"))
    )
    (net (code "129") (name "Net-(Z_RIGHT-Pad3)") (class "Default")
      (node (ref "Z_RIGHT") (pin "3") (pinfunction "3_3") (pintype "passive"))
      (node (ref "Z_RIGHT") (pin "4") (pinfunction "4_4") (pintype "passive"))
    )
    (net (code "130") (name "unconnected-(B1-0(RX0)-Pad0)") (class "Default")
      (node (ref "B1") (pin "0") (pinfunction "0(RX0)_0") (pintype "bidirectional"))
    )
    (net (code "131") (name "unconnected-(B1-1(TX0)-Pad1)") (class "Default")
      (node (ref "B1") (pin "1") (pinfunction "1(TX0)_1") (pintype "bidirectional"))
    )
    (net (code "132") (name "unconnected-(B1-14(TX3)-Pad14)") (class "Default")
      (node (ref "B1") (pin "14") (pinfunction "14(TX3)_14") (pintype "bidirectional"))
    )
    (net (code "133") (name "unconnected-(B1-15(RX3)-Pad15)") (class "Default")
      (node (ref "B1") (pin "15") (pinfunction "15(RX3)_15") (pintype "bidirectional"))
    )
    (net (code "134") (name "unconnected-(B1-16(TX2)-Pad16)") (class "Default")
      (node (ref "B1") (pin "16") (pinfunction "16(TX2)_16") (pintype "bidirectional"))
    )
    (net (code "135") (name "unconnected-(B1-17(RX2)-Pad17)") (class "Default")
      (node (ref "B1") (pin "17") (pinfunction "17(RX2)_17") (pintype "bidirectional"))
    )
    (net (code "136") (name "unconnected-(B1-18(TX1)-Pad18)") (class "Default")
      (node (ref "B1") (pin "18") (pinfunction "18(TX1)_18") (pintype "bidirectional"))
    )
    (net (code "137") (name "unconnected-(B1-19(RX1)-Pad19)") (class "Default")
      (node (ref "B1") (pin "19") (pinfunction "19(RX1)_19") (pintype "bidirectional"))
    )
    (net (code "138") (name "unconnected-(B1-20(SDA)-Pad20)") (class "Default")
      (node (ref "B1") (pin "20") (pinfunction "20(SDA)_20") (pintype "bidirectional"))
    )
    (net (code "139") (name "unconnected-(B1-21(SCL)-Pad21)") (class "Default")
      (node (ref "B1") (pin "21") (pinfunction "21(SCL)_21") (pintype "bidirectional"))
    )
    (net (code "140") (name "unconnected-(B1-A0(RX0)-PadA0)") (class "Default")
      (node (ref "B1") (pin "A0") (pinfunction "A0(RX0)_A0") (pintype "bidirectional"))
    )
    (net (code "141") (name "unconnected-(B1-Pad2)") (class "Default")
      (node (ref "B1") (pin "2") (pinfunction "2_2") (pintype "bidirectional"))
    )
    (net (code "142") (name "unconnected-(B1-Pad3)") (class "Default")
      (node (ref "B1") (pin "3") (pinfunction "3_3") (pintype "bidirectional"))
    )
    (net (code "143") (name "unconnected-(B1-Pad3.3V)") (class "Default")
      (node (ref "B1") (pin "3.3V") (pinfunction "3.3V_3.3V") (pintype "bidirectional"))
    )
    (net (code "144") (name "unconnected-(B1-Pad4)") (class "Default")
      (node (ref "B1") (pin "4") (pinfunction "4_4") (pintype "bidirectional"))
    )
    (net (code "145") (name "unconnected-(B1-Pad13)") (class "Default")
      (node (ref "B1") (pin "13") (pinfunction "13_13") (pintype "bidirectional"))
    )
    (net (code "146") (name "unconnected-(B1-PadAREF)") (class "Default")
      (node (ref "B1") (pin "AREF") (pinfunction "AREF_AREF") (pintype "bidirectional"))
    )
    (net (code "147") (name "unconnected-(B1-PadRESET)") (class "Default")
      (node (ref "B1") (pin "RESET") (pinfunction "RESET_RESET") (pintype "bidirectional"))
    )
    (net (code "148") (name "unconnected-(B1-PadVIN)") (class "Default")
      (node (ref "B1") (pin "VIN") (pinfunction "VIN_VIN") (pintype "bidirectional"))
    )
  )
)
